# Insoladora.net
KiCad netlist of a schematic drawn in EAGLE
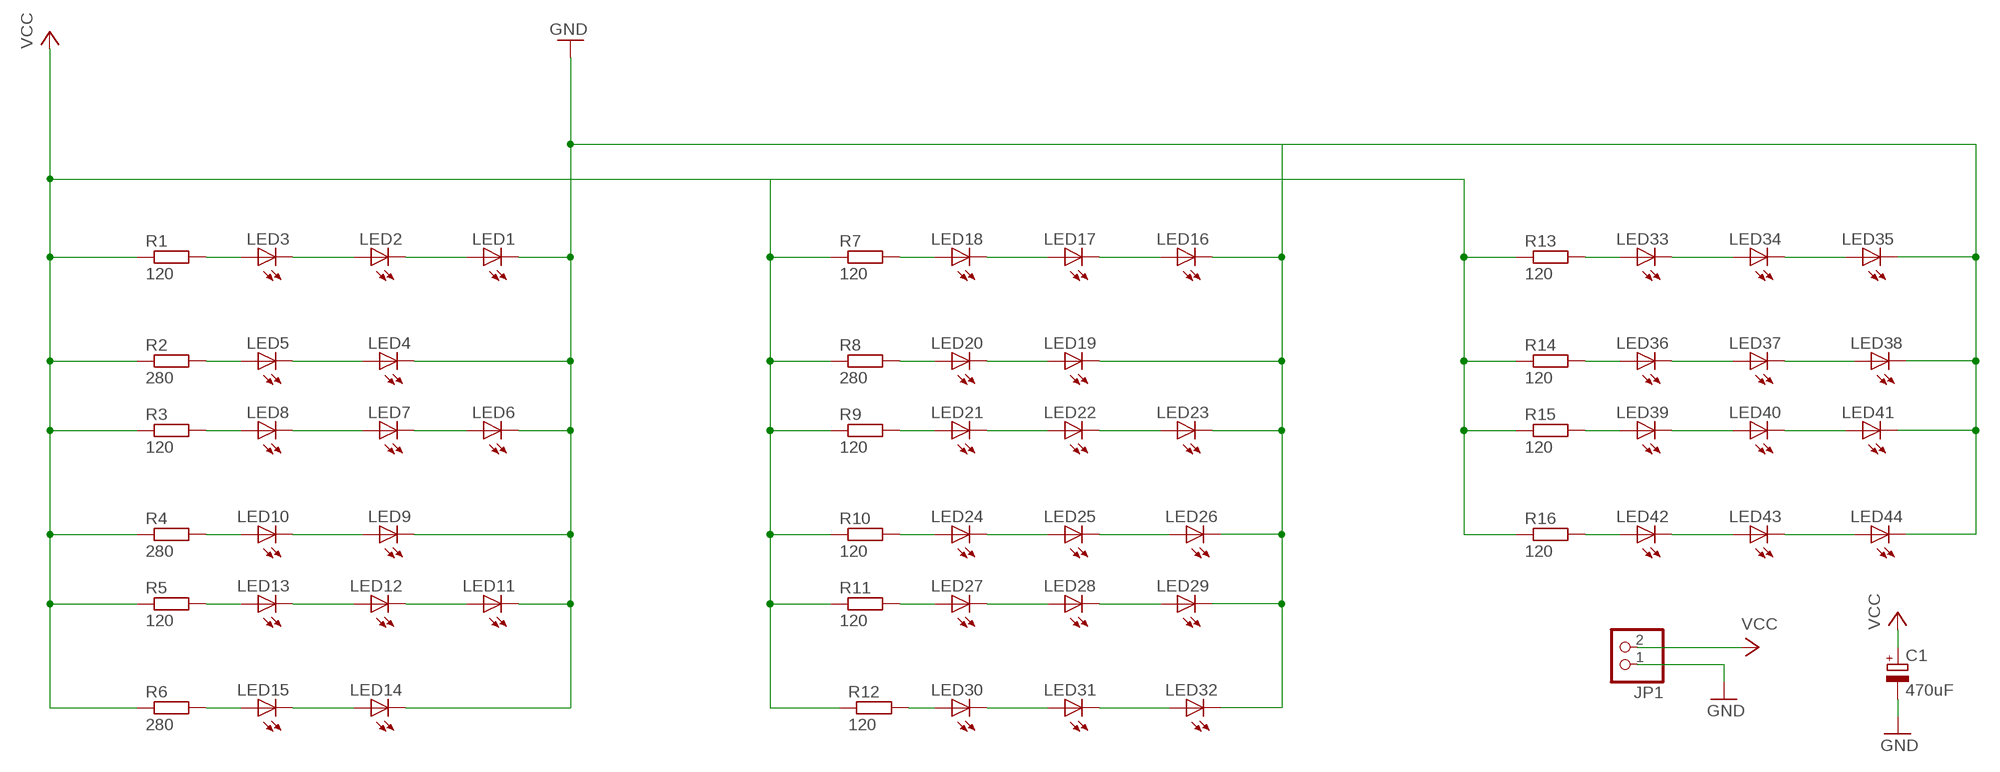
[diagram p0: schematic, sheet 1]

(export (version "E")
  (design (tool "Eeschema 10.0.6"))
  (components
    (comp (ref "C1")
      (value "470uF")
      (footprint "eagle-import:E2,5-7")
      (libsource (lib "eagle-import") (part "CPOL-EUE2.5-7"))
    )
    (comp (ref "JP1")
      (value "PINHD-1X2")
      (footprint "eagle-import:1X02")
      (libsource (lib "eagle-import") (part "PINHD-1X2"))
    )
    (comp (ref "LED1")
      (value "LED5MM")
      (footprint "eagle-import:LED5MM")
      (libsource (lib "eagle-import") (part "LED5MM"))
    )
    (comp (ref "LED2")
      (value "LED5MM")
      (footprint "eagle-import:LED5MM")
      (libsource (lib "eagle-import") (part "LED5MM"))
    )
    (comp (ref "LED3")
      (value "LED5MM")
      (footprint "eagle-import:LED5MM")
      (libsource (lib "eagle-import") (part "LED5MM"))
    )
    (comp (ref "LED4")
      (value "LED5MM")
      (footprint "eagle-import:LED5MM")
      (libsource (lib "eagle-import") (part "LED5MM"))
    )
    (comp (ref "LED5")
      (value "LED5MM")
      (footprint "eagle-import:LED5MM")
      (libsource (lib "eagle-import") (part "LED5MM"))
    )
    (comp (ref "LED6")
      (value "LED5MM")
      (footprint "eagle-import:LED5MM")
      (libsource (lib "eagle-import") (part "LED5MM"))
    )
    (comp (ref "LED7")
      (value "LED5MM")
      (footprint "eagle-import:LED5MM")
      (libsource (lib "eagle-import") (part "LED5MM"))
    )
    (comp (ref "LED8")
      (value "LED5MM")
      (footprint "eagle-import:LED5MM")
      (libsource (lib "eagle-import") (part "LED5MM"))
    )
    (comp (ref "LED9")
      (value "LED5MM")
      (footprint "eagle-import:LED5MM")
      (libsource (lib "eagle-import") (part "LED5MM"))
    )
    (comp (ref "LED10")
      (value "LED5MM")
      (footprint "eagle-import:LED5MM")
      (libsource (lib "eagle-import") (part "LED5MM"))
    )
    (comp (ref "LED11")
      (value "LED5MM")
      (footprint "eagle-import:LED5MM")
      (libsource (lib "eagle-import") (part "LED5MM"))
    )
    (comp (ref "LED12")
      (value "LED5MM")
      (footprint "eagle-import:LED5MM")
      (libsource (lib "eagle-import") (part "LED5MM"))
    )
    (comp (ref "LED13")
      (value "LED5MM")
      (footprint "eagle-import:LED5MM")
      (libsource (lib "eagle-import") (part "LED5MM"))
    )
    (comp (ref "LED14")
      (value "LED5MM")
      (footprint "eagle-import:LED5MM")
      (libsource (lib "eagle-import") (part "LED5MM"))
    )
    (comp (ref "LED15")
      (value "LED5MM")
      (footprint "eagle-import:LED5MM")
      (libsource (lib "eagle-import") (part "LED5MM"))
    )
    (comp (ref "LED16")
      (value "LED5MM")
      (footprint "eagle-import:LED5MM")
      (libsource (lib "eagle-import") (part "LED5MM"))
    )
    (comp (ref "LED17")
      (value "LED5MM")
      (footprint "eagle-import:LED5MM")
      (libsource (lib "eagle-import") (part "LED5MM"))
    )
    (comp (ref "LED18")
      (value "LED5MM")
      (footprint "eagle-import:LED5MM")
      (libsource (lib "eagle-import") (part "LED5MM"))
    )
    (comp (ref "LED19")
      (value "LED5MM")
      (footprint "eagle-import:LED5MM")
      (libsource (lib "eagle-import") (part "LED5MM"))
    )
    (comp (ref "LED20")
      (value "LED5MM")
      (footprint "eagle-import:LED5MM")
      (libsource (lib "eagle-import") (part "LED5MM"))
    )
    (comp (ref "LED21")
      (value "LED5MM")
      (footprint "eagle-import:LED5MM")
      (libsource (lib "eagle-import") (part "LED5MM"))
    )
    (comp (ref "LED22")
      (value "LED5MM")
      (footprint "eagle-import:LED5MM")
      (libsource (lib "eagle-import") (part "LED5MM"))
    )
    (comp (ref "LED23")
      (value "LED5MM")
      (footprint "eagle-import:LED5MM")
      (libsource (lib "eagle-import") (part "LED5MM"))
    )
    (comp (ref "LED24")
      (value "LED5MM")
      (footprint "eagle-import:LED5MM")
      (libsource (lib "eagle-import") (part "LED5MM"))
    )
    (comp (ref "LED25")
      (value "LED5MM")
      (footprint "eagle-import:LED5MM")
      (libsource (lib "eagle-import") (part "LED5MM"))
    )
    (comp (ref "LED26")
      (value "LED5MM")
      (footprint "eagle-import:LED5MM")
      (libsource (lib "eagle-import") (part "LED5MM"))
    )
    (comp (ref "LED27")
      (value "LED5MM")
      (footprint "eagle-import:LED5MM")
      (libsource (lib "eagle-import") (part "LED5MM"))
    )
    (comp (ref "LED28")
      (value "LED5MM")
      (footprint "eagle-import:LED5MM")
      (libsource (lib "eagle-import") (part "LED5MM"))
    )
    (comp (ref "LED29")
      (value "LED5MM")
      (footprint "eagle-import:LED5MM")
      (libsource (lib "eagle-import") (part "LED5MM"))
    )
    (comp (ref "LED30")
      (value "LED5MM")
      (footprint "eagle-import:LED5MM")
      (libsource (lib "eagle-import") (part "LED5MM"))
    )
    (comp (ref "LED31")
      (value "LED5MM")
      (footprint "eagle-import:LED5MM")
      (libsource (lib "eagle-import") (part "LED5MM"))
    )
    (comp (ref "LED32")
      (value "LED5MM")
      (footprint "eagle-import:LED5MM")
      (libsource (lib "eagle-import") (part "LED5MM"))
    )
    (comp (ref "LED33")
      (value "LED5MM")
      (footprint "eagle-import:LED5MM")
      (libsource (lib "eagle-import") (part "LED5MM"))
    )
    (comp (ref "LED34")
      (value "LED5MM")
      (footprint "eagle-import:LED5MM")
      (libsource (lib "eagle-import") (part "LED5MM"))
    )
    (comp (ref "LED35")
      (value "LED5MM")
      (footprint "eagle-import:LED5MM")
      (libsource (lib "eagle-import") (part "LED5MM"))
    )
    (comp (ref "LED36")
      (value "LED5MM")
      (footprint "eagle-import:LED5MM")
      (libsource (lib "eagle-import") (part "LED5MM"))
    )
    (comp (ref "LED37")
      (value "LED5MM")
      (footprint "eagle-import:LED5MM")
      (libsource (lib "eagle-import") (part "LED5MM"))
    )
    (comp (ref "LED38")
      (value "LED5MM")
      (footprint "eagle-import:LED5MM")
      (libsource (lib "eagle-import") (part "LED5MM"))
    )
    (comp (ref "LED39")
      (value "LED5MM")
      (footprint "eagle-import:LED5MM")
      (libsource (lib "eagle-import") (part "LED5MM"))
    )
    (comp (ref "LED40")
      (value "LED5MM")
      (footprint "eagle-import:LED5MM")
      (libsource (lib "eagle-import") (part "LED5MM"))
    )
    (comp (ref "LED41")
      (value "LED5MM")
      (footprint "eagle-import:LED5MM")
      (libsource (lib "eagle-import") (part "LED5MM"))
    )
    (comp (ref "LED42")
      (value "LED5MM")
      (footprint "eagle-import:LED5MM")
      (libsource (lib "eagle-import") (part "LED5MM"))
    )
    (comp (ref "LED43")
      (value "LED5MM")
      (footprint "eagle-import:LED5MM")
      (libsource (lib "eagle-import") (part "LED5MM"))
    )
    (comp (ref "LED44")
      (value "LED5MM")
      (footprint "eagle-import:LED5MM")
      (libsource (lib "eagle-import") (part "LED5MM"))
    )
    (comp (ref "R1")
      (value "120")
      (footprint "eagle-import:0207_10")
      (libsource (lib "eagle-import") (part "R-EU_0207/10"))
    )
    (comp (ref "R2")
      (value "280")
      (footprint "eagle-import:0207_10")
      (libsource (lib "eagle-import") (part "R-EU_0207/10"))
    )
    (comp (ref "R3")
      (value "120")
      (footprint "eagle-import:0207_10")
      (libsource (lib "eagle-import") (part "R-EU_0207/10"))
    )
    (comp (ref "R4")
      (value "280")
      (footprint "eagle-import:0207_10")
      (libsource (lib "eagle-import") (part "R-EU_0207/10"))
    )
    (comp (ref "R5")
      (value "120")
      (footprint "eagle-import:0207_10")
      (libsource (lib "eagle-import") (part "R-EU_0207/10"))
    )
    (comp (ref "R6")
      (value "280")
      (footprint "eagle-import:0207_10")
      (libsource (lib "eagle-import") (part "R-EU_0207/10"))
    )
    (comp (ref "R7")
      (value "120")
      (footprint "eagle-import:0207_10")
      (libsource (lib "eagle-import") (part "R-EU_0207/10"))
    )
    (comp (ref "R8")
      (value "280")
      (footprint "eagle-import:0207_10")
      (libsource (lib "eagle-import") (part "R-EU_0207/10"))
    )
    (comp (ref "R9")
      (value "120")
      (footprint "eagle-import:0207_10")
      (libsource (lib "eagle-import") (part "R-EU_0207/10"))
    )
    (comp (ref "R10")
      (value "120")
      (footprint "eagle-import:0207_10")
      (libsource (lib "eagle-import") (part "R-EU_0207/10"))
    )
    (comp (ref "R11")
      (value "120")
      (footprint "eagle-import:0207_10")
      (libsource (lib "eagle-import") (part "R-EU_0207/10"))
    )
    (comp (ref "R12")
      (value "120")
      (footprint "eagle-import:0207_10")
      (libsource (lib "eagle-import") (part "R-EU_0207/10"))
    )
    (comp (ref "R13")
      (value "120")
      (footprint "eagle-import:0207_10")
      (libsource (lib "eagle-import") (part "R-EU_0207/10"))
    )
    (comp (ref "R14")
      (value "120")
      (footprint "eagle-import:0207_10")
      (libsource (lib "eagle-import") (part "R-EU_0207/10"))
    )
    (comp (ref "R15")
      (value "120")
      (footprint "eagle-import:0207_10")
      (libsource (lib "eagle-import") (part "R-EU_0207/10"))
    )
    (comp (ref "R16")
      (value "120")
      (footprint "eagle-import:0207_10")
      (libsource (lib "eagle-import") (part "R-EU_0207/10"))
    )
  )
  (nets
    (net (code "1") (name "GND") (class "Default")
      (node (ref "C1") (pin "-") (pinfunction "-_-") (pintype "passive"))
      (node (ref "JP1") (pin "1") (pinfunction "1_1") (pintype "passive"))
      (node (ref "LED1") (pin "K") (pinfunction "C_K") (pintype "passive"))
      (node (ref "LED11") (pin "K") (pinfunction "C_K") (pintype "passive"))
      (node (ref "LED14") (pin "K") (pinfunction "C_K") (pintype "passive"))
      (node (ref "LED16") (pin "K") (pinfunction "C_K") (pintype "passive"))
      (node (ref "LED19") (pin "K") (pinfunction "C_K") (pintype "passive"))
      (node (ref "LED23") (pin "K") (pinfunction "C_K") (pintype "passive"))
      (node (ref "LED26") (pin "K") (pinfunction "C_K") (pintype "passive"))
      (node (ref "LED29") (pin "K") (pinfunction "C_K") (pintype "passive"))
      (node (ref "LED32") (pin "K") (pinfunction "C_K") (pintype "passive"))
      (node (ref "LED35") (pin "K") (pinfunction "C_K") (pintype "passive"))
      (node (ref "LED38") (pin "K") (pinfunction "C_K") (pintype "passive"))
      (node (ref "LED4") (pin "K") (pinfunction "C_K") (pintype "passive"))
      (node (ref "LED41") (pin "K") (pinfunction "C_K") (pintype "passive"))
      (node (ref "LED44") (pin "K") (pinfunction "C_K") (pintype "passive"))
      (node (ref "LED6") (pin "K") (pinfunction "C_K") (pintype "passive"))
      (node (ref "LED9") (pin "K") (pinfunction "C_K") (pintype "passive"))
    )
    (net (code "2") (name "Net-(LED2-C)") (class "Default")
      (node (ref "LED1") (pin "A") (pinfunction "A_A") (pintype "passive"))
      (node (ref "LED2") (pin "K") (pinfunction "C_K") (pintype "passive"))
    )
    (net (code "3") (name "Net-(LED3-C)") (class "Default")
      (node (ref "LED2") (pin "A") (pinfunction "A_A") (pintype "passive"))
      (node (ref "LED3") (pin "K") (pinfunction "C_K") (pintype "passive"))
    )
    (net (code "4") (name "Net-(LED3-PadA)") (class "Default")
      (node (ref "LED3") (pin "A") (pinfunction "A_A") (pintype "passive"))
      (node (ref "R1") (pin "2") (pinfunction "2_2") (pintype "passive"))
    )
    (net (code "5") (name "Net-(LED5-C)") (class "Default")
      (node (ref "LED4") (pin "A") (pinfunction "A_A") (pintype "passive"))
      (node (ref "LED5") (pin "K") (pinfunction "C_K") (pintype "passive"))
    )
    (net (code "6") (name "Net-(LED5-PadA)") (class "Default")
      (node (ref "LED5") (pin "A") (pinfunction "A_A") (pintype "passive"))
      (node (ref "R2") (pin "2") (pinfunction "2_2") (pintype "passive"))
    )
    (net (code "7") (name "Net-(LED7-C)") (class "Default")
      (node (ref "LED6") (pin "A") (pinfunction "A_A") (pintype "passive"))
      (node (ref "LED7") (pin "K") (pinfunction "C_K") (pintype "passive"))
    )
    (net (code "8") (name "Net-(LED8-C)") (class "Default")
      (node (ref "LED7") (pin "A") (pinfunction "A_A") (pintype "passive"))
      (node (ref "LED8") (pin "K") (pinfunction "C_K") (pintype "passive"))
    )
    (net (code "9") (name "Net-(LED8-PadA)") (class "Default")
      (node (ref "LED8") (pin "A") (pinfunction "A_A") (pintype "passive"))
      (node (ref "R3") (pin "2") (pinfunction "2_2") (pintype "passive"))
    )
    (net (code "10") (name "Net-(LED10-C)") (class "Default")
      (node (ref "LED10") (pin "K") (pinfunction "C_K") (pintype "passive"))
      (node (ref "LED9") (pin "A") (pinfunction "A_A") (pintype "passive"))
    )
    (net (code "11") (name "Net-(LED10-PadA)") (class "Default")
      (node (ref "LED10") (pin "A") (pinfunction "A_A") (pintype "passive"))
      (node (ref "R4") (pin "2") (pinfunction "2_2") (pintype "passive"))
    )
    (net (code "12") (name "Net-(LED12-C)") (class "Default")
      (node (ref "LED11") (pin "A") (pinfunction "A_A") (pintype "passive"))
      (node (ref "LED12") (pin "K") (pinfunction "C_K") (pintype "passive"))
    )
    (net (code "13") (name "Net-(LED13-C)") (class "Default")
      (node (ref "LED12") (pin "A") (pinfunction "A_A") (pintype "passive"))
      (node (ref "LED13") (pin "K") (pinfunction "C_K") (pintype "passive"))
    )
    (net (code "14") (name "Net-(LED13-PadA)") (class "Default")
      (node (ref "LED13") (pin "A") (pinfunction "A_A") (pintype "passive"))
      (node (ref "R5") (pin "2") (pinfunction "2_2") (pintype "passive"))
    )
    (net (code "15") (name "Net-(LED15-C)") (class "Default")
      (node (ref "LED14") (pin "A") (pinfunction "A_A") (pintype "passive"))
      (node (ref "LED15") (pin "K") (pinfunction "C_K") (pintype "passive"))
    )
    (net (code "16") (name "Net-(LED15-PadA)") (class "Default")
      (node (ref "LED15") (pin "A") (pinfunction "A_A") (pintype "passive"))
      (node (ref "R6") (pin "2") (pinfunction "2_2") (pintype "passive"))
    )
    (net (code "17") (name "Net-(LED17-C)") (class "Default")
      (node (ref "LED16") (pin "A") (pinfunction "A_A") (pintype "passive"))
      (node (ref "LED17") (pin "K") (pinfunction "C_K") (pintype "passive"))
    )
    (net (code "18") (name "Net-(LED18-C)") (class "Default")
      (node (ref "LED17") (pin "A") (pinfunction "A_A") (pintype "passive"))
      (node (ref "LED18") (pin "K") (pinfunction "C_K") (pintype "passive"))
    )
    (net (code "19") (name "Net-(LED18-PadA)") (class "Default")
      (node (ref "LED18") (pin "A") (pinfunction "A_A") (pintype "passive"))
      (node (ref "R7") (pin "2") (pinfunction "2_2") (pintype "passive"))
    )
    (net (code "20") (name "Net-(LED20-C)") (class "Default")
      (node (ref "LED19") (pin "A") (pinfunction "A_A") (pintype "passive"))
      (node (ref "LED20") (pin "K") (pinfunction "C_K") (pintype "passive"))
    )
    (net (code "21") (name "Net-(LED20-PadA)") (class "Default")
      (node (ref "LED20") (pin "A") (pinfunction "A_A") (pintype "passive"))
      (node (ref "R8") (pin "2") (pinfunction "2_2") (pintype "passive"))
    )
    (net (code "22") (name "Net-(LED21-C)") (class "Default")
      (node (ref "LED21") (pin "K") (pinfunction "C_K") (pintype "passive"))
      (node (ref "LED22") (pin "A") (pinfunction "A_A") (pintype "passive"))
    )
    (net (code "23") (name "Net-(LED21-PadA)") (class "Default")
      (node (ref "LED21") (pin "A") (pinfunction "A_A") (pintype "passive"))
      (node (ref "R9") (pin "2") (pinfunction "2_2") (pintype "passive"))
    )
    (net (code "24") (name "Net-(LED22-C)") (class "Default")
      (node (ref "LED22") (pin "K") (pinfunction "C_K") (pintype "passive"))
      (node (ref "LED23") (pin "A") (pinfunction "A_A") (pintype "passive"))
    )
    (net (code "25") (name "Net-(LED24-C)") (class "Default")
      (node (ref "LED24") (pin "K") (pinfunction "C_K") (pintype "passive"))
      (node (ref "LED25") (pin "A") (pinfunction "A_A") (pintype "passive"))
    )
    (net (code "26") (name "Net-(LED24-PadA)") (class "Default")
      (node (ref "LED24") (pin "A") (pinfunction "A_A") (pintype "passive"))
      (node (ref "R10") (pin "2") (pinfunction "2_2") (pintype "passive"))
    )
    (net (code "27") (name "Net-(LED25-C)") (class "Default")
      (node (ref "LED25") (pin "K") (pinfunction "C_K") (pintype "passive"))
      (node (ref "LED26") (pin "A") (pinfunction "A_A") (pintype "passive"))
    )
    (net (code "28") (name "Net-(LED27-C)") (class "Default")
      (node (ref "LED27") (pin "K") (pinfunction "C_K") (pintype "passive"))
      (node (ref "LED28") (pin "A") (pinfunction "A_A") (pintype "passive"))
    )
    (net (code "29") (name "Net-(LED27-PadA)") (class "Default")
      (node (ref "LED27") (pin "A") (pinfunction "A_A") (pintype "passive"))
      (node (ref "R11") (pin "2") (pinfunction "2_2") (pintype "passive"))
    )
    (net (code "30") (name "Net-(LED28-C)") (class "Default")
      (node (ref "LED28") (pin "K") (pinfunction "C_K") (pintype "passive"))
      (node (ref "LED29") (pin "A") (pinfunction "A_A") (pintype "passive"))
    )
    (net (code "31") (name "Net-(LED30-C)") (class "Default")
      (node (ref "LED30") (pin "K") (pinfunction "C_K") (pintype "passive"))
      (node (ref "LED31") (pin "A") (pinfunction "A_A") (pintype "passive"))
    )
    (net (code "32") (name "Net-(LED30-PadA)") (class "Default")
      (node (ref "LED30") (pin "A") (pinfunction "A_A") (pintype "passive"))
      (node (ref "R12") (pin "2") (pinfunction "2_2") (pintype "passive"))
    )
    (net (code "33") (name "Net-(LED31-C)") (class "Default")
      (node (ref "LED31") (pin "K") (pinfunction "C_K") (pintype "passive"))
      (node (ref "LED32") (pin "A") (pinfunction "A_A") (pintype "passive"))
    )
    (net (code "34") (name "Net-(LED33-C)") (class "Default")
      (node (ref "LED33") (pin "K") (pinfunction "C_K") (pintype "passive"))
      (node (ref "LED34") (pin "A") (pinfunction "A_A") (pintype "passive"))
    )
    (net (code "35") (name "Net-(LED33-PadA)") (class "Default")
      (node (ref "LED33") (pin "A") (pinfunction "A_A") (pintype "passive"))
      (node (ref "R13") (pin "2") (pinfunction "2_2") (pintype "passive"))
    )
    (net (code "36") (name "Net-(LED34-C)") (class "Default")
      (node (ref "LED34") (pin "K") (pinfunction "C_K") (pintype "passive"))
      (node (ref "LED35") (pin "A") (pinfunction "A_A") (pintype "passive"))
    )
    (net (code "37") (name "Net-(LED36-C)") (class "Default")
      (node (ref "LED36") (pin "K") (pinfunction "C_K") (pintype "passive"))
      (node (ref "LED37") (pin "A") (pinfunction "A_A") (pintype "passive"))
    )
    (net (code "38") (name "Net-(LED36-PadA)") (class "Default")
      (node (ref "LED36") (pin "A") (pinfunction "A_A") (pintype "passive"))
      (node (ref "R14") (pin "2") (pinfunction "2_2") (pintype "passive"))
    )
    (net (code "39") (name "Net-(LED37-C)") (class "Default")
      (node (ref "LED37") (pin "K") (pinfunction "C_K") (pintype "passive"))
      (node (ref "LED38") (pin "A") (pinfunction "A_A") (pintype "passive"))
    )
    (net (code "40") (name "Net-(LED39-C)") (class "Default")
      (node (ref "LED39") (pin "K") (pinfunction "C_K") (pintype "passive"))
      (node (ref "LED40") (pin "A") (pinfunction "A_A") (pintype "passive"))
    )
    (net (code "41") (name "Net-(LED39-PadA)") (class "Default")
      (node (ref "LED39") (pin "A") (pinfunction "A_A") (pintype "passive"))
      (node (ref "R15") (pin "2") (pinfunction "2_2") (pintype "passive"))
    )
    (net (code "42") (name "Net-(LED40-C)") (class "Default")
      (node (ref "LED40") (pin "K") (pinfunction "C_K") (pintype "passive"))
      (node (ref "LED41") (pin "A") (pinfunction "A_A") (pintype "passive"))
    )
    (net (code "43") (name "Net-(LED42-C)") (class "Default")
      (node (ref "LED42") (pin "K") (pinfunction "C_K") (pintype "passive"))
      (node (ref "LED43") (pin "A") (pinfunction "A_A") (pintype "passive"))
    )
    (net (code "44") (name "Net-(LED42-PadA)") (class "Default")
      (node (ref "LED42") (pin "A") (pinfunction "A_A") (pintype "passive"))
      (node (ref "R16") (pin "2") (pinfunction "2_2") (pintype "passive"))
    )
    (net (code "45") (name "Net-(LED43-C)") (class "Default")
      (node (ref "LED43") (pin "K") (pinfunction "C_K") (pintype "passive"))
      (node (ref "LED44") (pin "A") (pinfunction "A_A") (pintype "passive"))
    )
    (net (code "46") (name "VCC") (class "Default")
      (node (ref "C1") (pin "+") (pinfunction "+_+") (pintype "passive"))
      (node (ref "JP1") (pin "2") (pinfunction "2_2") (pintype "passive"))
      (node (ref "R1") (pin "1") (pinfunction "1_1") (pintype "passive"))
      (node (ref "R10") (pin "1") (pinfunction "1_1") (pintype "passive"))
      (node (ref "R11") (pin "1") (pinfunction "1_1") (pintype "passive"))
      (node (ref "R12") (pin "1") (pinfunction "1_1") (pintype "passive"))
      (node (ref "R13") (pin "1") (pinfunction "1_1") (pintype "passive"))
      (node (ref "R14") (pin "1") (pinfunction "1_1") (pintype "passive"))
      (node (ref "R15") (pin "1") (pinfunction "1_1") (pintype "passive"))
      (node (ref "R16") (pin "1") (pinfunction "1_1") (pintype "passive"))
      (node (ref "R2") (pin "1") (pinfunction "1_1") (pintype "passive"))
      (node (ref "R3") (pin "1") (pinfunction "1_1") (pintype "passive"))
      (node (ref "R4") (pin "1") (pinfunction "1_1") (pintype "passive"))
      (node (ref "R5") (pin "1") (pinfunction "1_1") (pintype "passive"))
      (node (ref "R6") (pin "1") (pinfunction "1_1") (pintype "passive"))
      (node (ref "R7") (pin "1") (pinfunction "1_1") (pintype "passive"))
      (node (ref "R8") (pin "1") (pinfunction "1_1") (pintype "passive"))
      (node (ref "R9") (pin "1") (pinfunction "1_1") (pintype "passive"))
    )
  )
)
